# Shutter_Hall_Sensors_Test.net
KiCad netlist of a schematic drawn in EAGLE
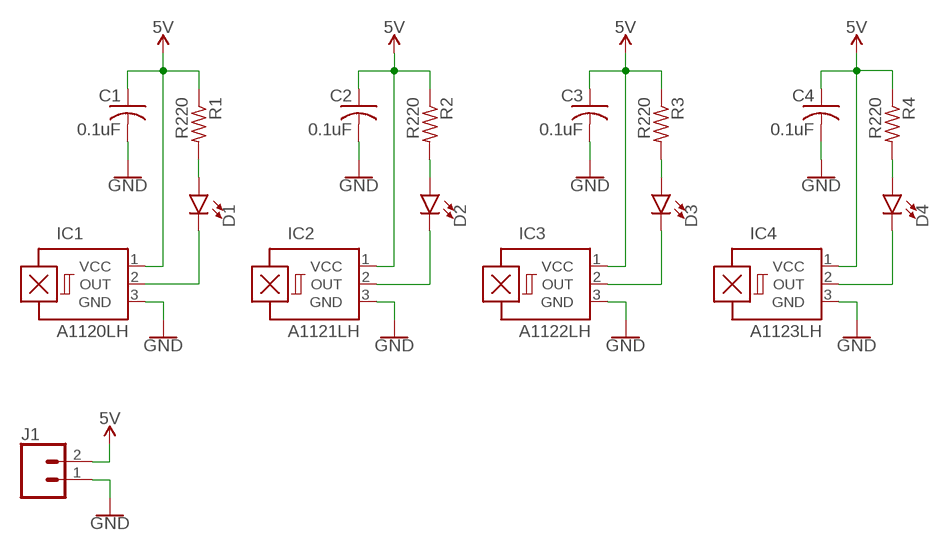
[diagram p0: schematic, sheet 1]

(export (version "E")
  (design (tool "Eeschema 10.0.6"))
  (components
    (comp (ref "C1")
      (value "0.1uF")
      (footprint "eagle-import:C0805")
      (libsource (lib "eagle-import") (part "C-USC0805"))
    )
    (comp (ref "C2")
      (value "0.1uF")
      (footprint "eagle-import:C0805")
      (libsource (lib "eagle-import") (part "C-USC0805"))
    )
    (comp (ref "C3")
      (value "0.1uF")
      (footprint "eagle-import:C0805")
      (libsource (lib "eagle-import") (part "C-USC0805"))
    )
    (comp (ref "C4")
      (value "0.1uF")
      (footprint "eagle-import:C0805")
      (libsource (lib "eagle-import") (part "C-USC0805"))
    )
    (comp (ref "D1")
      (value "LED5MM")
      (footprint "eagle-import:LED_5MM")
      (libsource (lib "eagle-import") (part "LED5MM"))
    )
    (comp (ref "D2")
      (value "LED5MM")
      (footprint "eagle-import:LED_5MM")
      (libsource (lib "eagle-import") (part "LED5MM"))
    )
    (comp (ref "D3")
      (value "LED5MM")
      (footprint "eagle-import:LED_5MM")
      (libsource (lib "eagle-import") (part "LED5MM"))
    )
    (comp (ref "D4")
      (value "LED5MM")
      (footprint "eagle-import:LED_5MM")
      (libsource (lib "eagle-import") (part "LED5MM"))
    )
    (comp (ref "IC1")
      (value "A1120LH")
      (footprint "eagle-import:SOT23-W")
      (fields (field (name "MF") "ALLEGRO MICROSYSTEMS, INC.") (field (name "MPN") "A1203LLHLT-T"))
      (libsource (lib "eagle-import") (part "A12?LH03"))
    )
    (comp (ref "IC2")
      (value "A1121LH")
      (footprint "eagle-import:SOT23-W")
      (fields (field (name "MF") "ALLEGRO MICROSYSTEMS, INC.") (field (name "MPN") "A1203LLHLT-T"))
      (libsource (lib "eagle-import") (part "A12?LH03"))
    )
    (comp (ref "IC3")
      (value "A1122LH")
      (footprint "eagle-import:SOT23-W")
      (fields (field (name "MF") "ALLEGRO MICROSYSTEMS, INC.") (field (name "MPN") "A1203LLHLT-T"))
      (libsource (lib "eagle-import") (part "A12?LH03"))
    )
    (comp (ref "IC4")
      (value "A1123LH")
      (footprint "eagle-import:SOT23-W")
      (fields (field (name "MF") "ALLEGRO MICROSYSTEMS, INC.") (field (name "MPN") "A1203LLHLT-T"))
      (libsource (lib "eagle-import") (part "A12?LH03"))
    )
    (comp (ref "J1")
      (value "CONN_02")
      (footprint "eagle-import:1X02")
      (libsource (lib "eagle-import") (part "CONN_02"))
    )
    (comp (ref "R1")
      (value "R220")
      (footprint "eagle-import:R0805")
      (libsource (lib "eagle-import") (part "R-US_R0805"))
    )
    (comp (ref "R2")
      (value "R220")
      (footprint "eagle-import:R0805")
      (libsource (lib "eagle-import") (part "R-US_R0805"))
    )
    (comp (ref "R3")
      (value "R220")
      (footprint "eagle-import:R0805")
      (libsource (lib "eagle-import") (part "R-US_R0805"))
    )
    (comp (ref "R4")
      (value "R220")
      (footprint "eagle-import:R0805")
      (libsource (lib "eagle-import") (part "R-US_R0805"))
    )
  )
  (nets
    (net (code "1") (name "5V") (class "Default")
      (node (ref "C1") (pin "1") (pinfunction "1_1") (pintype "passive"))
      (node (ref "C2") (pin "1") (pinfunction "1_1") (pintype "passive"))
      (node (ref "C3") (pin "1") (pinfunction "1_1") (pintype "passive"))
      (node (ref "C4") (pin "1") (pinfunction "1_1") (pintype "passive"))
      (node (ref "IC1") (pin "1") (pinfunction "VCC_1") (pintype "power_in"))
      (node (ref "IC2") (pin "1") (pinfunction "VCC_1") (pintype "power_in"))
      (node (ref "IC3") (pin "1") (pinfunction "VCC_1") (pintype "power_in"))
      (node (ref "IC4") (pin "1") (pinfunction "VCC_1") (pintype "power_in"))
      (node (ref "J1") (pin "2") (pinfunction "2_2") (pintype "passive"))
      (node (ref "R1") (pin "1") (pinfunction "1_1") (pintype "passive"))
      (node (ref "R2") (pin "1") (pinfunction "1_1") (pintype "passive"))
      (node (ref "R3") (pin "1") (pinfunction "1_1") (pintype "passive"))
      (node (ref "R4") (pin "1") (pinfunction "1_1") (pintype "passive"))
    )
    (net (code "2") (name "GND") (class "Default")
      (node (ref "C1") (pin "2") (pinfunction "2_2") (pintype "passive"))
      (node (ref "C2") (pin "2") (pinfunction "2_2") (pintype "passive"))
      (node (ref "C3") (pin "2") (pinfunction "2_2") (pintype "passive"))
      (node (ref "C4") (pin "2") (pinfunction "2_2") (pintype "passive"))
      (node (ref "IC1") (pin "3") (pinfunction "GND_3") (pintype "power_in"))
      (node (ref "IC2") (pin "3") (pinfunction "GND_3") (pintype "power_in"))
      (node (ref "IC3") (pin "3") (pinfunction "GND_3") (pintype "power_in"))
      (node (ref "IC4") (pin "3") (pinfunction "GND_3") (pintype "power_in"))
      (node (ref "J1") (pin "1") (pinfunction "1_1") (pintype "passive"))
    )
    (net (code "3") (name "Net-(D1-C)") (class "Default")
      (node (ref "D1") (pin "K") (pinfunction "C_K") (pintype "passive"))
      (node (ref "IC1") (pin "2") (pinfunction "OUT_2") (pintype "output"))
    )
    (net (code "4") (name "Net-(D1-PadA)") (class "Default")
      (node (ref "D1") (pin "A") (pinfunction "A_A") (pintype "passive"))
      (node (ref "R1") (pin "2") (pinfunction "2_2") (pintype "passive"))
    )
    (net (code "5") (name "Net-(D2-C)") (class "Default")
      (node (ref "D2") (pin "K") (pinfunction "C_K") (pintype "passive"))
      (node (ref "IC2") (pin "2") (pinfunction "OUT_2") (pintype "output"))
    )
    (net (code "6") (name "Net-(D2-PadA)") (class "Default")
      (node (ref "D2") (pin "A") (pinfunction "A_A") (pintype "passive"))
      (node (ref "R2") (pin "2") (pinfunction "2_2") (pintype "passive"))
    )
    (net (code "7") (name "Net-(D3-C)") (class "Default")
      (node (ref "D3") (pin "K") (pinfunction "C_K") (pintype "passive"))
      (node (ref "IC3") (pin "2") (pinfunction "OUT_2") (pintype "output"))
    )
    (net (code "8") (name "Net-(D3-PadA)") (class "Default")
      (node (ref "D3") (pin "A") (pinfunction "A_A") (pintype "passive"))
      (node (ref "R3") (pin "2") (pinfunction "2_2") (pintype "passive"))
    )
    (net (code "9") (name "Net-(D4-C)") (class "Default")
      (node (ref "D4") (pin "K") (pinfunction "C_K") (pintype "passive"))
      (node (ref "IC4") (pin "2") (pinfunction "OUT_2") (pintype "output"))
    )
    (net (code "10") (name "Net-(D4-PadA)") (class "Default")
      (node (ref "D4") (pin "A") (pinfunction "A_A") (pintype "passive"))
      (node (ref "R4") (pin "2") (pinfunction "2_2") (pintype "passive"))
    )
  )
)
